# CBL003.net
KiCad netlist of a schematic drawn in Altium Designer
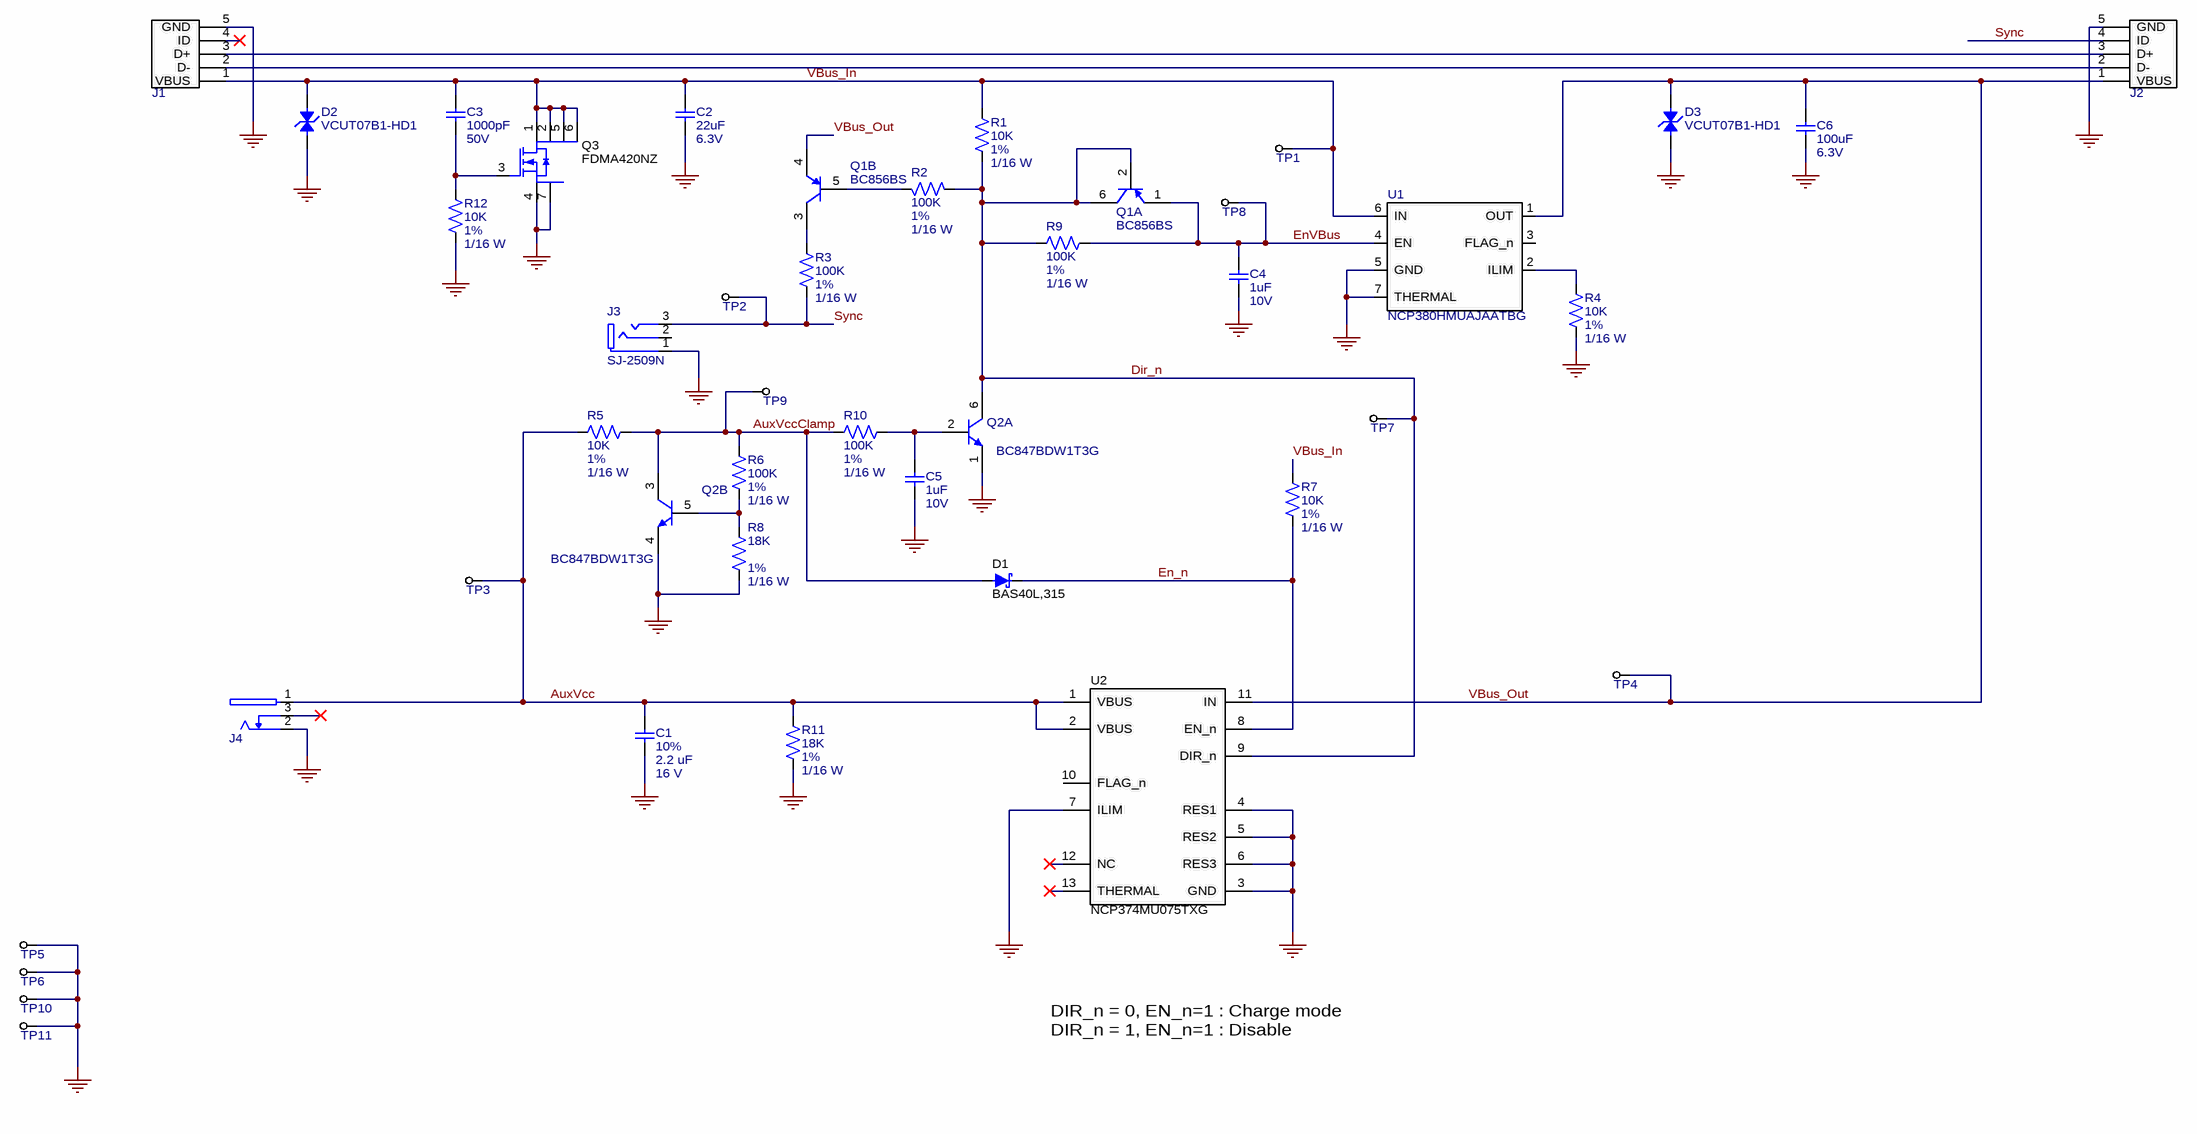
[diagram p0: CBL003.SchDoc]

(export (version "E")
  (design (tool "Eeschema 10.0.6"))
  (components
    (comp (ref "C1")
      (value "2.2 uF")
      (footprint "CAP_CERAMIC_0603")
      (description "='CAP, ' + Material + ', ' + Value + ', ' + Tolerance + ', '  + Voltage + ', ' + Package")
      (fields
        (field (name "MANUFACTURER") "TDK")
        (field (name "TOLERANCE") "10%")
        (field (name "VOLTAGE") "16 V")
        (field (name "Comment") "CAP, X7R, 2.2 uF, 10%, 16 V, 0603")
      )
      (libsource (lib "master") (part "CAP-NONPOL"))
    )
    (comp (ref "C2")
      (value "2.2E-5")
      (footprint "CAP_CERAMIC_0805")
      (description "CAP, CERAMIC, 22UF, ±20%, 6.3V, X5R, 0805")
      (fields
        (field (name "MANUFACTURER") "Murata")
        (field (name "VALUE_TEXT_UNITS") "22uF")
        (field (name "VOLTAGE_RATING_TEXT") "6.3V")
        (field (name "PARTNUMBER") "120-000023")
      )
      (libsource (lib "OVR_Altium") (part "CAP-NONPOL"))
    )
    (comp (ref "C3")
      (value "1E-9")
      (footprint "CAP_CERAMIC_0603")
      (description "CAP, CERAMIC, 1000PF, ±10%, 50V, C0G, 0603")
      (fields
        (field (name "MANUFACTURER") "Murata")
        (field (name "VALUE_TEXT_UNITS") "1000pF")
        (field (name "VOLTAGE_RATING_TEXT") "50V")
        (field (name "PARTNUMBER") "120-000031")
      )
      (libsource (lib "OVR_Altium") (part "CAP-NONPOL"))
    )
    (comp (ref "C4")
      (value "1E-6")
      (footprint "CAP_CERAMIC_0402")
      (description "CAP, CERAMIC, 1uF, ±10%, 10V, X5R, 0402")
      (fields
        (field (name "MANUFACTURER") "Murata")
        (field (name "VALUE_TEXT_UNITS") "1uF")
        (field (name "VOLTAGE_RATING_TEXT") "10V")
        (field (name "PARTNUMBER") "120-000010")
      )
      (libsource (lib "OVR_Altium") (part "CAP, CERAMIC"))
    )
    (comp (ref "C5")
      (value "1E-6")
      (footprint "CAP_CERAMIC_0402")
      (description "CAP, CERAMIC, 1uF, ±10%, 10V, X5R, 0402")
      (fields
        (field (name "MANUFACTURER") "Murata")
        (field (name "VALUE_TEXT_UNITS") "1uF")
        (field (name "VOLTAGE_RATING_TEXT") "10V")
        (field (name "PARTNUMBER") "120-000010")
      )
      (libsource (lib "OVR_Altium") (part "CAP, CERAMIC"))
    )
    (comp (ref "C6")
      (value "0.0001")
      (footprint "CAP_CERAMIC_1206")
      (description "CAP, CERAMIC, 100UF, ±20%, 6.3V, X5R, 1206")
      (fields
        (field (name "MANUFACTURER") "Murata")
        (field (name "VALUE_TEXT_UNITS") "100uF")
        (field (name "VOLTAGE_RATING_TEXT") "6.3V")
        (field (name "PARTNUMBER") "120-000030")
      )
      (libsource (lib "OVR_Altium") (part "CAP-NONPOL"))
    )
    (comp (ref "D1")
      (value "BAS40L,315")
      (footprint "SOD882")
      (description "DIODE, SCHOTTKY, 40V, SOD882")
      (fields (field (name "PARTNUMBER") "150-000003") (field (name "MANUFACTURER") "NXP"))
      (libsource (lib "OVR_Altium") (part "DIODE_SCHOTTKY"))
    )
    (comp (ref "D2")
      (value "VCUT07B1-HD1")
      (footprint "Diodes:LLP1006-2L")
      (description "DIODE, ESD SUPPRESSOR, SINGLE LINE BI-DIRECTIONAL, LLP1006-2L")
      (fields (field (name "MANUFACTURER") "Vishay"))
      (libsource (lib "Diodes") (part "VCUT07B1-HD1"))
    )
    (comp (ref "D3")
      (value "VCUT07B1-HD1")
      (footprint "Diodes:LLP1006-2L")
      (description "DIODE, ESD SUPPRESSOR, SINGLE LINE BI-DIRECTIONAL, LLP1006-2L")
      (fields (field (name "MANUFACTURER") "Vishay"))
      (libsource (lib "Diodes") (part "VCUT07B1-HD1"))
    )
    (comp (ref "J1")
      (value "USB_WIRE_MOUNT")
      (footprint "USB_WIRE_MOUNT")
      (libsource (lib "") (part "USB_WIRE_MOUNT_1"))
    )
    (comp (ref "J2")
      (value "USB_WIRE_MOUNT")
      (footprint "USB_WIRE_MOUNT")
      (libsource (lib "master") (part "USB_WIRE_MOUNT"))
    )
    (comp (ref "J3")
      (value "SJ-2509N")
      (footprint "CUI_SJ2509N")
      (description "CONN, 2.5MM AUDIO JACK")
      (fields (field (name "MANUFACTURER") "CUI"))
      (libsource (lib "master") (part "AUDIO_JACK_3P"))
    )
    (comp (ref "J4")
      (value "DC Jack")
      (footprint "KLDX-0202")
      (description "CONN, DC POWER JACK")
      (fields (field (name "MANUFACTURER") "Kycon"))
      (libsource (lib "master") (part "DC_JACK"))
    )
    (comp (ref "Q1")
      (value "TRANSISTOR, DUAL PNP, SOT363")
      (footprint "SOT363")
      (description "='TRANSISTOR, DUAL PNP, ' + Package")
      (fields (field (name "MANUFACTURER") "NXP") (field (name "MANUFACTURER_PN") "BC856BS"))
      (libsource (lib "master") (part "PNP_DUAL"))
    )
    (comp (ref "Q2")
      (value "TRANSISTOR, DUAL NPN, SOT363")
      (footprint "SOT363")
      (description "='TRANSISTOR, DUAL NPN, ' + Package")
      (fields (field (name "MANUFACTURER") "ON Semi") (field (name "MANUFACTURER_PN") "BC847BDW1T3G"))
      (libsource (lib "master") (part "NPN_DUAL"))
    )
    (comp (ref "Q3")
      (value "FDMA420NZ")
      (footprint "DFN2020-6")
      (description "TRANS, NMOS, DFN2020-6")
      (fields
        (field (name "PARTNUMBER") "170-000003")
        (field (name "MANUFACTURER") "Fairchild Semiconductor")
      )
      (libsource (lib "OVR_Altium") (part "NMOS_DFN2020-6"))
    )
    (comp (ref "R1")
      (value "10K")
      (footprint "RESISTOR_0402")
      (description "='RES, ' + Package + ', ' + Value + ', ' + Tolerance + ', '  + Power")
      (fields
        (field (name "MANUFACTURER") "Yageo")
        (field (name "TOLERANCE") "1%")
        (field (name "POWER") "1/16 W")
        (field (name "Comment") "RES, 0402, 10K, 1%, 1/16 W")
      )
      (libsource (lib "master") (part "RESISTOR"))
    )
    (comp (ref "R2")
      (value "100K")
      (footprint "RESISTOR_0402")
      (description "='RES, ' + Package + ', ' + Value + ', ' + Tolerance + ', '  + Power")
      (fields
        (field (name "MANUFACTURER") "KOA Speer")
        (field (name "TOLERANCE") "1%")
        (field (name "POWER") "1/16 W")
        (field (name "Comment") "RES, 0402, 100K, 1%, 1/16 W")
      )
      (libsource (lib "master") (part "RESISTOR"))
    )
    (comp (ref "R3")
      (value "100K")
      (footprint "RESISTOR_0402")
      (description "='RES, ' + Package + ', ' + Value + ', ' + Tolerance + ', '  + Power")
      (fields
        (field (name "MANUFACTURER") "KOA Speer")
        (field (name "TOLERANCE") "1%")
        (field (name "POWER") "1/16 W")
        (field (name "Comment") "RES, 0402, 100K, 1%, 1/16 W")
      )
      (libsource (lib "master") (part "RESISTOR"))
    )
    (comp (ref "R4")
      (value "10K")
      (footprint "RESISTOR_0402")
      (description "='RES, ' + Package + ', ' + Value + ', ' + Tolerance + ', '  + Power")
      (fields
        (field (name "MANUFACTURER") "Yageo")
        (field (name "TOLERANCE") "1%")
        (field (name "POWER") "1/16 W")
        (field (name "Comment") "RES, 0402, 10K, 1%, 1/16 W")
      )
      (libsource (lib "master") (part "RESISTOR"))
    )
    (comp (ref "R5")
      (value "10K")
      (footprint "RESISTOR_0402")
      (description "='RES, ' + Package + ', ' + Value + ', ' + Tolerance + ', '  + Power")
      (fields
        (field (name "MANUFACTURER") "Yageo")
        (field (name "TOLERANCE") "1%")
        (field (name "POWER") "1/16 W")
        (field (name "Comment") "RES, 0402, 10K, 1%, 1/16 W")
      )
      (libsource (lib "master") (part "RESISTOR"))
    )
    (comp (ref "R6")
      (value "100K")
      (footprint "RESISTOR_0402")
      (description "='RES, ' + Package + ', ' + Value + ', ' + Tolerance + ', '  + Power")
      (fields
        (field (name "MANUFACTURER") "KOA Speer")
        (field (name "TOLERANCE") "1%")
        (field (name "POWER") "1/16 W")
        (field (name "Comment") "RES, 0402, 100K, 1%, 1/16 W")
      )
      (libsource (lib "master") (part "RESISTOR"))
    )
    (comp (ref "R7")
      (value "10K")
      (footprint "RESISTOR_0402")
      (description "='RES, ' + Package + ', ' + Value + ', ' + Tolerance + ', '  + Power")
      (fields
        (field (name "MANUFACTURER") "Yageo")
        (field (name "TOLERANCE") "1%")
        (field (name "POWER") "1/16 W")
        (field (name "Comment") "RES, 0402, 10K, 1%, 1/16 W")
      )
      (libsource (lib "master") (part "RESISTOR"))
    )
    (comp (ref "R8")
      (value "18K")
      (footprint "RESISTOR_0402")
      (description "='RES, ' + Package + ', ' + Value + ', ' + Tolerance + ', '  + Power")
      (fields
        (field (name "MANUFACTURER") "Yageo")
        (field (name "TOLERANCE") "1%")
        (field (name "POWER") "1/16 W")
        (field (name "Comment") "RES, 0402, 18K, 1%, 1/16 W")
      )
      (libsource (lib "master") (part "RESISTOR"))
    )
    (comp (ref "R9")
      (value "100K")
      (footprint "RESISTOR_0402")
      (description "='RES, ' + Package + ', ' + Value + ', ' + Tolerance + ', '  + Power")
      (fields
        (field (name "MANUFACTURER") "KOA Speer")
        (field (name "TOLERANCE") "1%")
        (field (name "POWER") "1/16 W")
        (field (name "Comment") "RES, 0402, 100K, 1%, 1/16 W")
      )
      (libsource (lib "master") (part "RESISTOR"))
    )
    (comp (ref "R10")
      (value "100K")
      (footprint "RESISTOR_0402")
      (description "='RES, ' + Package + ', ' + Value + ', ' + Tolerance + ', '  + Power")
      (fields
        (field (name "MANUFACTURER") "KOA Speer")
        (field (name "TOLERANCE") "1%")
        (field (name "POWER") "1/16 W")
        (field (name "Comment") "RES, 0402, 100K, 1%, 1/16 W")
      )
      (libsource (lib "master") (part "RESISTOR"))
    )
    (comp (ref "R11")
      (value "18K")
      (footprint "RESISTOR_0402")
      (description "='RES, ' + Package + ', ' + Value + ', ' + Tolerance + ', '  + Power")
      (fields
        (field (name "MANUFACTURER") "Yageo")
        (field (name "TOLERANCE") "1%")
        (field (name "POWER") "1/16 W")
        (field (name "Comment") "RES, 0402, 18K, 1%, 1/16 W")
      )
      (libsource (lib "master") (part "RESISTOR"))
    )
    (comp (ref "R12")
      (value "10K")
      (footprint "RESISTOR_0402")
      (description "='RES, ' + Package + ', ' + Value + ', ' + Tolerance + ', '  + Power")
      (fields
        (field (name "MANUFACTURER") "Yageo")
        (field (name "TOLERANCE") "1%")
        (field (name "POWER") "1/16 W")
        (field (name "Comment") "RES, 0402, 10K, 1%, 1/16 W")
      )
      (libsource (lib "master") (part "RESISTOR"))
    )
    (comp (ref "TP1")
      (value "TESTPOINT")
      (footprint "TESTPOINT40")
      (libsource (lib "master") (part "TESTPOINT"))
    )
    (comp (ref "TP2")
      (value "TESTPOINT")
      (footprint "TESTPOINT40")
      (libsource (lib "master") (part "TESTPOINT"))
    )
    (comp (ref "TP3")
      (value "TESTPOINT")
      (footprint "TESTPOINT40")
      (libsource (lib "master") (part "TESTPOINT"))
    )
    (comp (ref "TP4")
      (value "TESTPOINT")
      (footprint "TESTPOINT40")
      (libsource (lib "master") (part "TESTPOINT"))
    )
    (comp (ref "TP5")
      (value "TESTPOINT")
      (footprint "TESTPOINT40")
      (libsource (lib "master") (part "TESTPOINT"))
    )
    (comp (ref "TP6")
      (value "TESTPOINT")
      (footprint "TESTPOINT40")
      (libsource (lib "master") (part "TESTPOINT"))
    )
    (comp (ref "TP7")
      (value "TESTPOINT")
      (footprint "TESTPOINT40")
      (libsource (lib "master") (part "TESTPOINT"))
    )
    (comp (ref "TP8")
      (value "TESTPOINT")
      (footprint "TESTPOINT40")
      (libsource (lib "master") (part "TESTPOINT"))
    )
    (comp (ref "TP9")
      (value "TESTPOINT")
      (footprint "TESTPOINT40")
      (libsource (lib "master") (part "TESTPOINT"))
    )
    (comp (ref "TP10")
      (value "TESTPOINT")
      (footprint "TESTPOINT40")
      (libsource (lib "master") (part "TESTPOINT"))
    )
    (comp (ref "TP11")
      (value "TESTPOINT")
      (footprint "TESTPOINT40")
      (libsource (lib "master") (part "TESTPOINT"))
    )
    (comp (ref "U1")
      (value "NCP380HMUAJAATBG")
      (footprint "DFN200X200X050-6")
      (description "IC, LOAD SWITCH, UDFN6")
      (fields (field (name "MANUFACTURER") "ON Semi") (field (name "MANUFACTURER_PN") "NCP380HMUAJAATBG"))
      (libsource (lib "master") (part "NCP380"))
    )
    (comp (ref "U2")
      (value "NCP374MU075TXG")
      (footprint "LLGA12-NCP374")
      (description "IC, LOAD SWITCH WITH OVP/RVP, LLGA-12")
      (fields (field (name "MANUFACTURER") "ON Semiconductor") (field (name "PARTNUMBER") "300-000021"))
      (libsource (lib "OVR_Altium") (part "NCP374"))
    )
  )
  (nets
    (net (code "1") (name "/AuxVcc") (class "Default")
      (node (ref "C1") (pin "1") (pinfunction "1_1") (pintype "passive"))
      (node (ref "J4") (pin "1") (pinfunction "1_1") (pintype "passive"))
      (node (ref "R11") (pin "1") (pinfunction "1_1") (pintype "passive"))
      (node (ref "R5") (pin "1") (pinfunction "1_1") (pintype "passive"))
      (node (ref "TP3") (pin "1") (pinfunction "1_1") (pintype "passive"))
      (node (ref "U2") (pin "1") (pinfunction "VBUS_1") (pintype "passive"))
      (node (ref "U2") (pin "2") (pinfunction "VBUS_2") (pintype "passive"))
    )
    (net (code "2") (name "/AuxVccClamp") (class "Default")
      (node (ref "D1") (pin "1") (pinfunction "A_1") (pintype "passive"))
      (node (ref "Q2") (pin "3") (pinfunction "C2_3") (pintype "passive"))
      (node (ref "R10") (pin "1") (pinfunction "1_1") (pintype "passive"))
      (node (ref "R5") (pin "2") (pinfunction "2_2") (pintype "passive"))
      (node (ref "R6") (pin "2") (pinfunction "2_2") (pintype "passive"))
      (node (ref "TP9") (pin "1") (pinfunction "1_1") (pintype "passive"))
    )
    (net (code "3") (name "/Dir_n") (class "Default")
      (node (ref "Q1") (pin "2") (pinfunction "B_2") (pintype "passive"))
      (node (ref "Q1") (pin "6") (pinfunction "C_6") (pintype "passive"))
      (node (ref "Q2") (pin "6") (pinfunction "C1_6") (pintype "passive"))
      (node (ref "R1") (pin "1") (pinfunction "1_1") (pintype "passive"))
      (node (ref "R2") (pin "1") (pinfunction "1_1") (pintype "passive"))
      (node (ref "R9") (pin "2") (pinfunction "2_2") (pintype "passive"))
      (node (ref "TP7") (pin "1") (pinfunction "1_1") (pintype "passive"))
      (node (ref "U2") (pin "9") (pinfunction "DIR_n_9") (pintype "passive"))
    )
    (net (code "4") (name "/EnVBus") (class "Default")
      (node (ref "C4") (pin "1") (pinfunction "1_1") (pintype "passive"))
      (node (ref "Q1") (pin "1") (pinfunction "E_1") (pintype "passive"))
      (node (ref "R9") (pin "1") (pinfunction "1_1") (pintype "passive"))
      (node (ref "TP8") (pin "1") (pinfunction "1_1") (pintype "passive"))
      (node (ref "U1") (pin "4") (pinfunction "EN_4") (pintype "passive"))
    )
    (net (code "5") (name "/En_n") (class "Default")
      (node (ref "D1") (pin "2") (pinfunction "C_2") (pintype "passive"))
      (node (ref "R7") (pin "2") (pinfunction "2_2") (pintype "passive"))
      (node (ref "U2") (pin "8") (pinfunction "EN_n_8") (pintype "passive"))
    )
    (net (code "6") (name "/Sync") (class "Default")
      (node (ref "J2") (pin "4") (pinfunction "ID_4") (pintype "passive"))
      (node (ref "J3") (pin "3") (pinfunction "3_3") (pintype "passive"))
      (node (ref "R3") (pin "1") (pinfunction "1_1") (pintype "passive"))
      (node (ref "TP2") (pin "1") (pinfunction "1_1") (pintype "passive"))
    )
    (net (code "7") (name "/VBus_In") (class "Default")
      (node (ref "C2") (pin "1") (pinfunction "1_1") (pintype "passive"))
      (node (ref "C3") (pin "1") (pinfunction "1_1") (pintype "passive"))
      (node (ref "D2") (pin "1") (pintype "passive"))
      (node (ref "J1") (pin "1") (pinfunction "VBUS_1") (pintype "passive"))
      (node (ref "Q3") (pin "1") (pinfunction "S_1") (pintype "passive"))
      (node (ref "Q3") (pin "2") (pinfunction "S_2") (pintype "passive"))
      (node (ref "Q3") (pin "5") (pinfunction "D_5") (pintype "passive"))
      (node (ref "Q3") (pin "6") (pinfunction "D_6") (pintype "passive"))
      (node (ref "R1") (pin "2") (pinfunction "2_2") (pintype "passive"))
      (node (ref "R7") (pin "1") (pinfunction "1_1") (pintype "passive"))
      (node (ref "TP1") (pin "1") (pinfunction "1_1") (pintype "passive"))
      (node (ref "U1") (pin "6") (pinfunction "IN_6") (pintype "passive"))
    )
    (net (code "8") (name "/VBus_Out") (class "Default")
      (node (ref "C6") (pin "1") (pinfunction "1_1") (pintype "passive"))
      (node (ref "D3") (pin "1") (pintype "passive"))
      (node (ref "J2") (pin "1") (pinfunction "VBUS_1") (pintype "passive"))
      (node (ref "Q1") (pin "4") (pinfunction "E_4") (pintype "passive"))
      (node (ref "TP4") (pin "1") (pinfunction "1_1") (pintype "passive"))
      (node (ref "U1") (pin "1") (pinfunction "OUT_1") (pintype "passive"))
      (node (ref "U2") (pin "11") (pinfunction "IN_11") (pintype "passive"))
    )
    (net (code "9") (name "GND") (class "Default")
      (node (ref "C1") (pin "2") (pinfunction "2_2") (pintype "passive"))
      (node (ref "C2") (pin "2") (pinfunction "2_2") (pintype "passive"))
      (node (ref "C4") (pin "2") (pinfunction "2_2") (pintype "passive"))
      (node (ref "C5") (pin "2") (pinfunction "2_2") (pintype "passive"))
      (node (ref "C6") (pin "2") (pinfunction "2_2") (pintype "passive"))
      (node (ref "D2") (pin "2") (pintype "passive"))
      (node (ref "D3") (pin "2") (pintype "passive"))
      (node (ref "J1") (pin "5") (pinfunction "GND_5") (pintype "passive"))
      (node (ref "J2") (pin "5") (pinfunction "GND_5") (pintype "passive"))
      (node (ref "J3") (pin "1") (pinfunction "1_1") (pintype "passive"))
      (node (ref "J4") (pin "2") (pinfunction "2_2") (pintype "passive"))
      (node (ref "Q2") (pin "1") (pinfunction "E1_1") (pintype "passive"))
      (node (ref "Q2") (pin "4") (pinfunction "E2_4") (pintype "passive"))
      (node (ref "Q3") (pin "4") (pinfunction "G_4") (pintype "passive"))
      (node (ref "Q3") (pin "7") (pinfunction "D_7") (pintype "passive"))
      (node (ref "R11") (pin "2") (pinfunction "2_2") (pintype "passive"))
      (node (ref "R12") (pin "1") (pinfunction "1_1") (pintype "passive"))
      (node (ref "R4") (pin "1") (pinfunction "1_1") (pintype "passive"))
      (node (ref "R8") (pin "1") (pinfunction "1_1") (pintype "passive"))
      (node (ref "TP10") (pin "1") (pinfunction "1_1") (pintype "passive"))
      (node (ref "TP11") (pin "1") (pinfunction "1_1") (pintype "passive"))
      (node (ref "TP5") (pin "1") (pinfunction "1_1") (pintype "passive"))
      (node (ref "TP6") (pin "1") (pinfunction "1_1") (pintype "passive"))
      (node (ref "U1") (pin "5") (pinfunction "GND_5") (pintype "passive"))
      (node (ref "U1") (pin "7") (pinfunction "THERMAL_7") (pintype "passive"))
      (node (ref "U2") (pin "3") (pinfunction "GND_3") (pintype "passive"))
      (node (ref "U2") (pin "4") (pinfunction "RES1_4") (pintype "passive"))
      (node (ref "U2") (pin "5") (pinfunction "RES2_5") (pintype "passive"))
      (node (ref "U2") (pin "6") (pinfunction "RES3_6") (pintype "passive"))
      (node (ref "U2") (pin "7") (pinfunction "ILIM_7") (pintype "passive"))
    )
    (net (code "10") (name "Net-(C3-Pad2)") (class "Default")
      (node (ref "C3") (pin "2") (pinfunction "2_2") (pintype "passive"))
      (node (ref "Q3") (pin "3") (pinfunction "S_3") (pintype "passive"))
      (node (ref "R12") (pin "2") (pinfunction "2_2") (pintype "passive"))
    )
    (net (code "11") (name "Net-(J1-D+)") (class "Default")
      (node (ref "J1") (pin "3") (pinfunction "D+_3") (pintype "passive"))
      (node (ref "J2") (pin "3") (pinfunction "D+_3") (pintype "passive"))
    )
    (net (code "12") (name "Net-(J1-D-)") (class "Default")
      (node (ref "J1") (pin "2") (pinfunction "D-_2") (pintype "passive"))
      (node (ref "J2") (pin "2") (pinfunction "D-_2") (pintype "passive"))
    )
    (net (code "13") (name "Net-(Q1B-B)") (class "Default")
      (node (ref "Q1") (pin "5") (pinfunction "B_5") (pintype "passive"))
      (node (ref "R2") (pin "2") (pinfunction "2_2") (pintype "passive"))
    )
    (net (code "14") (name "Net-(Q1B-C)") (class "Default")
      (node (ref "Q1") (pin "3") (pinfunction "C_3") (pintype "passive"))
      (node (ref "R3") (pin "2") (pinfunction "2_2") (pintype "passive"))
    )
    (net (code "15") (name "Net-(Q2A-B1)") (class "Default")
      (node (ref "C5") (pin "1") (pinfunction "1_1") (pintype "passive"))
      (node (ref "Q2") (pin "2") (pinfunction "B1_2") (pintype "passive"))
      (node (ref "R10") (pin "2") (pinfunction "2_2") (pintype "passive"))
    )
    (net (code "16") (name "Net-(Q2B-B2)") (class "Default")
      (node (ref "Q2") (pin "5") (pinfunction "B2_5") (pintype "passive"))
      (node (ref "R6") (pin "1") (pinfunction "1_1") (pintype "passive"))
      (node (ref "R8") (pin "2") (pinfunction "2_2") (pintype "passive"))
    )
    (net (code "17") (name "Net-(U1-ILIM)") (class "Default")
      (node (ref "R4") (pin "2") (pinfunction "2_2") (pintype "passive"))
      (node (ref "U1") (pin "2") (pinfunction "ILIM_2") (pintype "passive"))
    )
    (net (code "18") (name "unconnected-(J1-ID-Pad4)") (class "Default")
      (node (ref "J1") (pin "4") (pinfunction "ID_4") (pintype "passive+no_connect"))
    )
    (net (code "19") (name "unconnected-(J3-Pad2)") (class "Default")
      (node (ref "J3") (pin "2") (pinfunction "2_2") (pintype "passive"))
    )
    (net (code "20") (name "unconnected-(J4-Pad3)") (class "Default")
      (node (ref "J4") (pin "3") (pinfunction "3_3") (pintype "passive+no_connect"))
    )
    (net (code "21") (name "unconnected-(U1-FLAG_n-Pad3)") (class "Default")
      (node (ref "U1") (pin "3") (pinfunction "FLAG_n_3") (pintype "passive"))
    )
    (net (code "22") (name "unconnected-(U2-FLAG_n-Pad10)") (class "Default")
      (node (ref "U2") (pin "10") (pinfunction "FLAG_n_10") (pintype "passive"))
    )
    (net (code "23") (name "unconnected-(U2-NC-Pad12)") (class "Default")
      (node (ref "U2") (pin "12") (pinfunction "NC_12") (pintype "passive+no_connect"))
    )
    (net (code "24") (name "unconnected-(U2-THERMAL-Pad13)") (class "Default")
      (node (ref "U2") (pin "13") (pinfunction "THERMAL_13") (pintype "passive+no_connect"))
    )
  )
)
